# Microcontroller_board_Photodiode_plate.net
KiCad netlist of a schematic drawn in EasyEDA
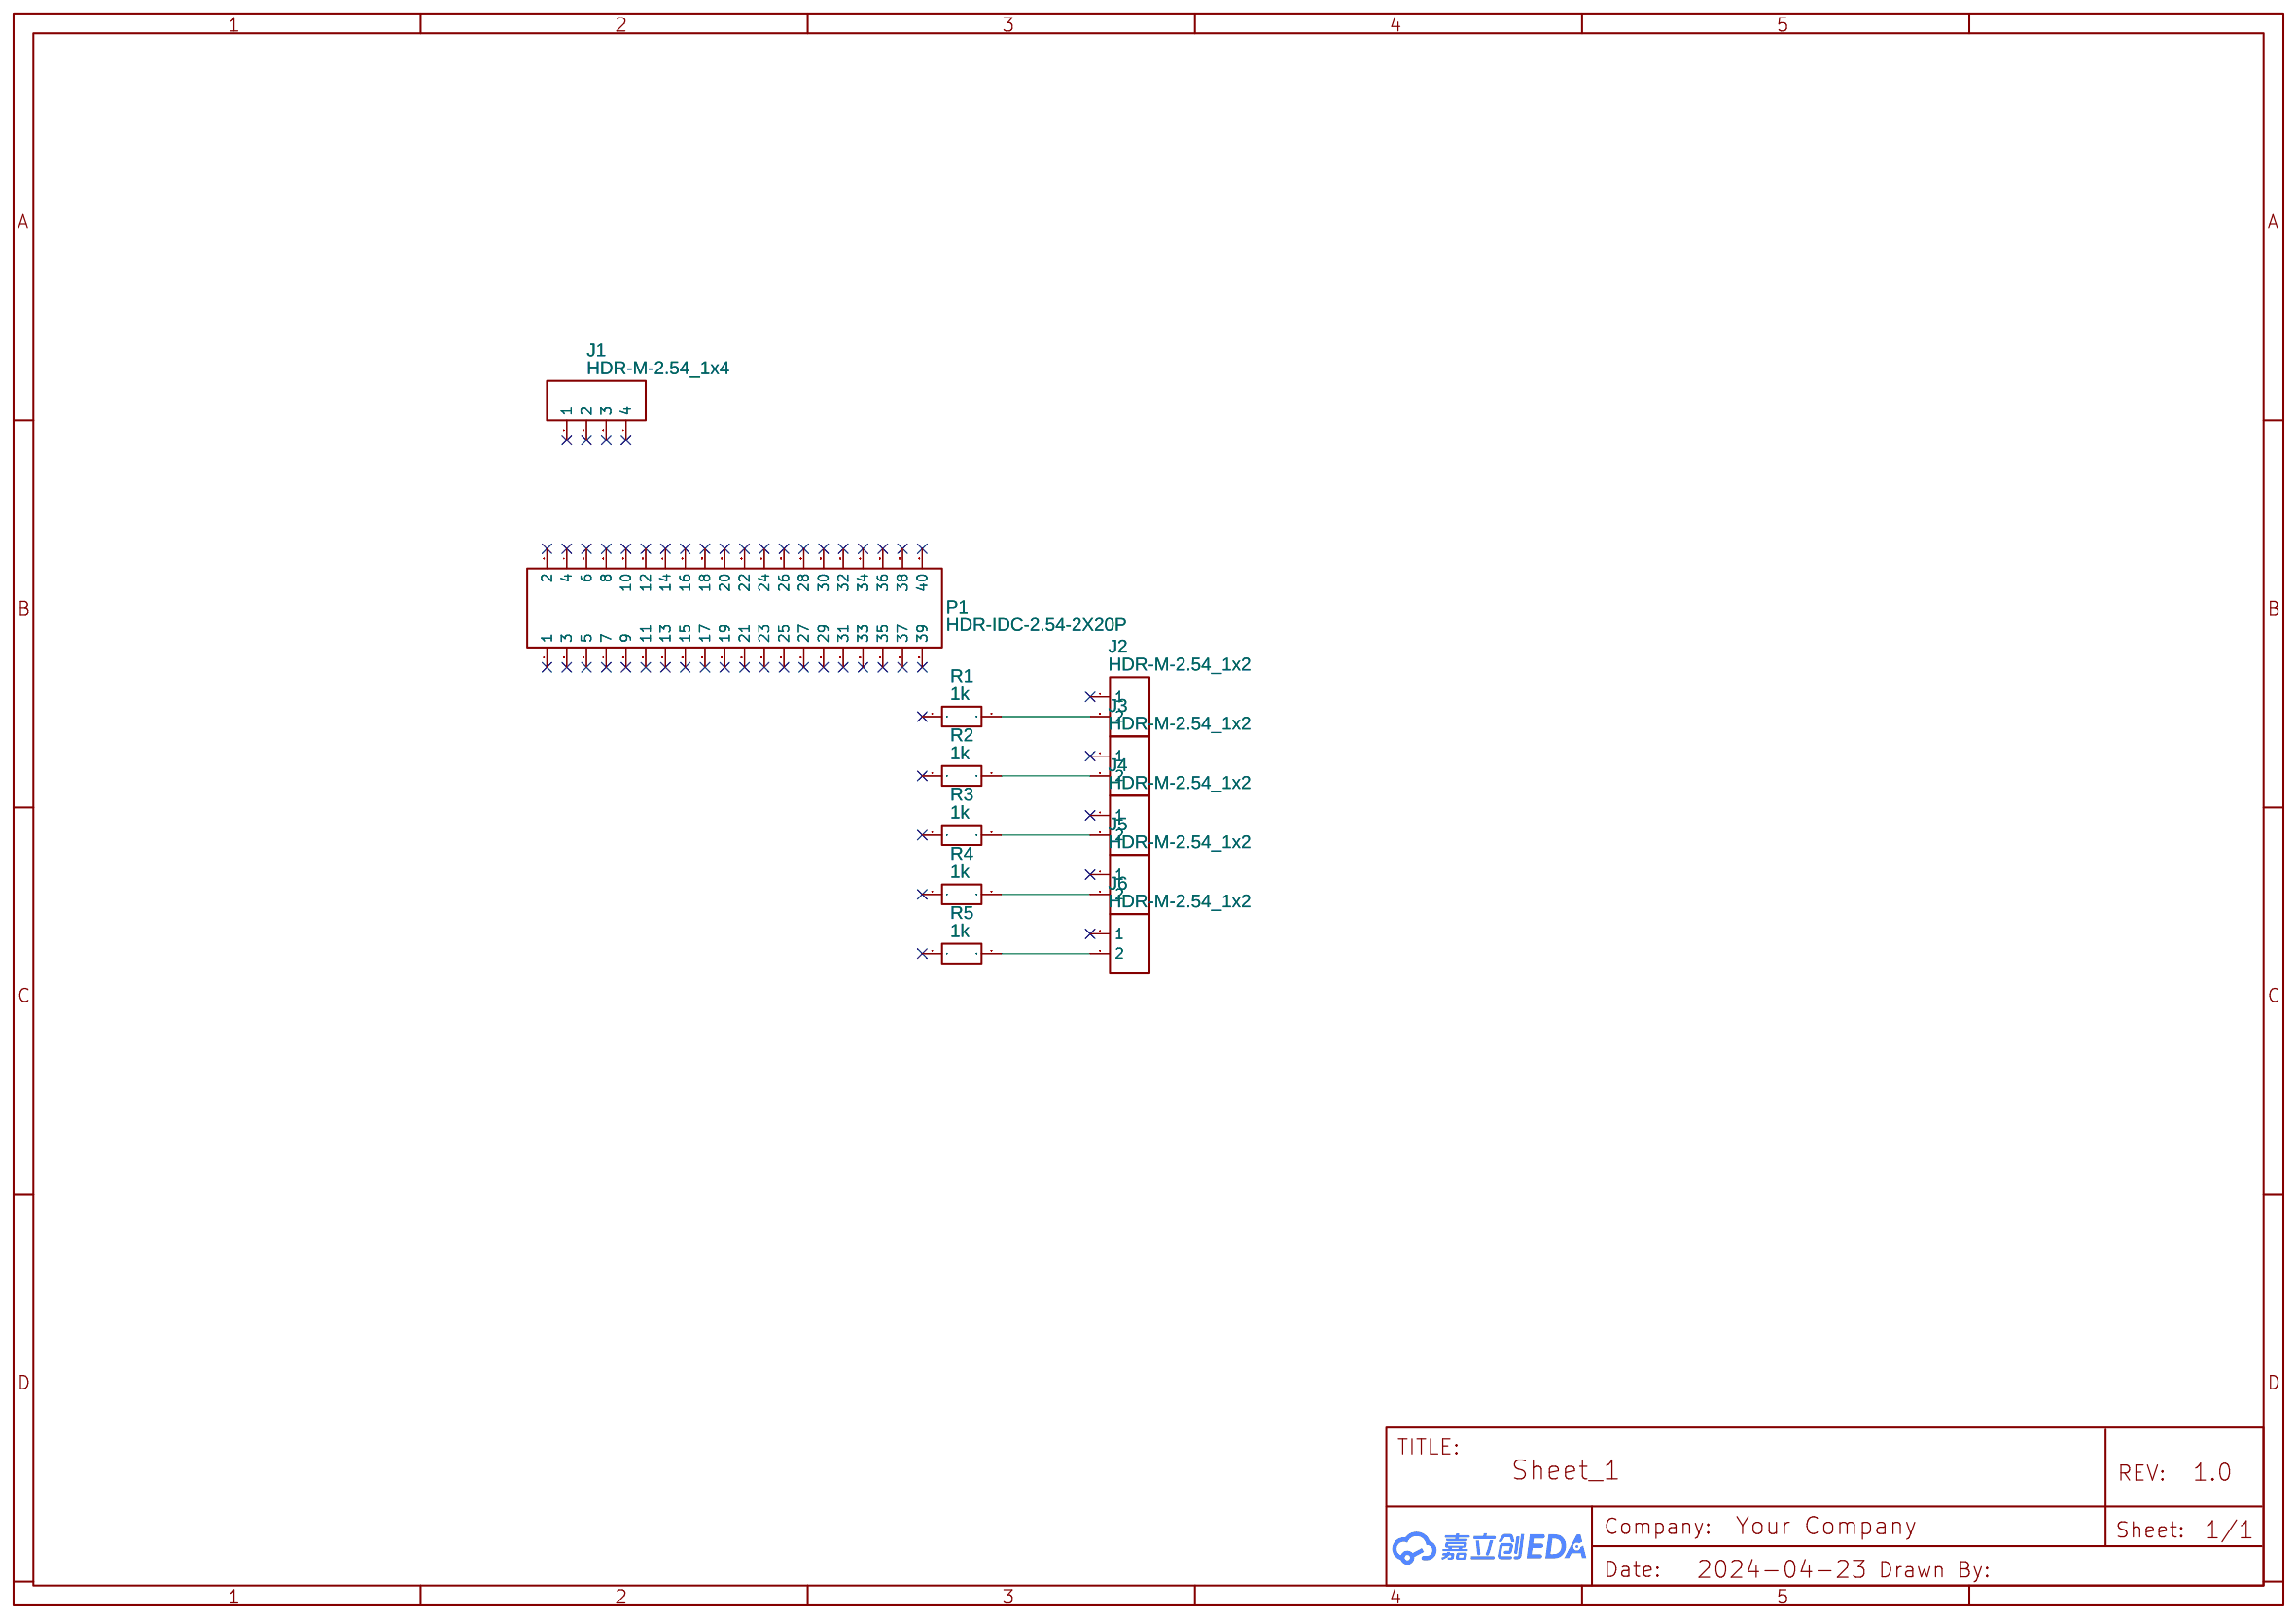
[diagram p0: schematic sheet]

(export (version "E")
  (design (tool "Eeschema 10.0.6"))
  (components
    (comp (ref "J1")
      (value "HDR-M-2.54_1x4")
      (fields (field (name "BOM_Supplier Part") "C124378"))
      (libsource (lib "") (part "HDR-M-2.54_1x4"))
    )
    (comp (ref "J2")
      (value "HDR-M-2.54_1x2")
      (fields (field (name "BOM_Supplier Part") "C124375"))
      (libsource (lib "") (part "HDR-M-2.54_1x2"))
    )
    (comp (ref "J3")
      (value "HDR-M-2.54_1x2")
      (fields (field (name "BOM_Supplier Part") "C124375"))
      (libsource (lib "") (part "HDR-M-2.54_1x2"))
    )
    (comp (ref "J4")
      (value "HDR-M-2.54_1x2")
      (fields (field (name "BOM_Supplier Part") "C124375"))
      (libsource (lib "") (part "HDR-M-2.54_1x2"))
    )
    (comp (ref "J5")
      (value "HDR-M-2.54_1x2")
      (fields (field (name "BOM_Supplier Part") "C124375"))
      (libsource (lib "") (part "HDR-M-2.54_1x2"))
    )
    (comp (ref "J6")
      (value "HDR-M-2.54_1x2")
      (fields (field (name "BOM_Supplier Part") "C124375"))
      (libsource (lib "") (part "HDR-M-2.54_1x2"))
    )
    (comp (ref "P1")
      (value "HDR-IDC-2.54-2X20P")
      (fields
        (field (name "BOM_Manufacturer Part") "IDC Box 2X20 2.54MM")
        (field (name "BOM_Supplier Part") "C9138")
      )
      (libsource (lib "") (part "HDR-IDC-2.54-2X20P"))
    )
    (comp (ref "R1") (value "1k") (libsource (lib "") (part "R_AXIAL-0.3_EU")))
    (comp (ref "R2") (value "1k") (libsource (lib "") (part "R_AXIAL-0.3_EU")))
    (comp (ref "R3") (value "1k") (libsource (lib "") (part "R_AXIAL-0.3_EU")))
    (comp (ref "R4") (value "1k") (libsource (lib "") (part "R_AXIAL-0.3_EU")))
    (comp (ref "R5") (value "1k") (libsource (lib "") (part "R_AXIAL-0.3_EU")))
  )
  (nets
    (net (code "1") (name "Net-(J2-Pad2)") (class "Default")
      (node (ref "J2") (pin "2") (pinfunction "2_2") (pintype "unspecified"))
      (node (ref "R1") (pin "2") (pinfunction "2_2") (pintype "unspecified"))
    )
    (net (code "2") (name "Net-(J3-Pad2)") (class "Default")
      (node (ref "J3") (pin "2") (pinfunction "2_2") (pintype "unspecified"))
      (node (ref "R2") (pin "2") (pinfunction "2_2") (pintype "unspecified"))
    )
    (net (code "3") (name "Net-(J4-Pad2)") (class "Default")
      (node (ref "J4") (pin "2") (pinfunction "2_2") (pintype "unspecified"))
      (node (ref "R3") (pin "2") (pinfunction "2_2") (pintype "unspecified"))
    )
    (net (code "4") (name "Net-(J5-Pad2)") (class "Default")
      (node (ref "J5") (pin "2") (pinfunction "2_2") (pintype "unspecified"))
      (node (ref "R4") (pin "2") (pinfunction "2_2") (pintype "unspecified"))
    )
    (net (code "5") (name "Net-(J6-Pad2)") (class "Default")
      (node (ref "J6") (pin "2") (pinfunction "2_2") (pintype "unspecified"))
      (node (ref "R5") (pin "2") (pinfunction "2_2") (pintype "unspecified"))
    )
    (net (code "6") (name "unconnected-(J1-Pad1)") (class "Default")
      (node (ref "J1") (pin "1") (pinfunction "1_1") (pintype "unspecified+no_connect"))
    )
    (net (code "7") (name "unconnected-(J1-Pad2)") (class "Default")
      (node (ref "J1") (pin "2") (pinfunction "2_2") (pintype "unspecified+no_connect"))
    )
    (net (code "8") (name "unconnected-(J1-Pad3)") (class "Default")
      (node (ref "J1") (pin "3") (pinfunction "3_3") (pintype "unspecified+no_connect"))
    )
    (net (code "9") (name "unconnected-(J1-Pad4)") (class "Default")
      (node (ref "J1") (pin "4") (pinfunction "4_4") (pintype "unspecified+no_connect"))
    )
    (net (code "10") (name "unconnected-(J2-Pad1)") (class "Default")
      (node (ref "J2") (pin "1") (pinfunction "1_1") (pintype "unspecified+no_connect"))
    )
    (net (code "11") (name "unconnected-(J3-Pad1)") (class "Default")
      (node (ref "J3") (pin "1") (pinfunction "1_1") (pintype "unspecified+no_connect"))
    )
    (net (code "12") (name "unconnected-(J4-Pad1)") (class "Default")
      (node (ref "J4") (pin "1") (pinfunction "1_1") (pintype "unspecified+no_connect"))
    )
    (net (code "13") (name "unconnected-(J5-Pad1)") (class "Default")
      (node (ref "J5") (pin "1") (pinfunction "1_1") (pintype "unspecified+no_connect"))
    )
    (net (code "14") (name "unconnected-(J6-Pad1)") (class "Default")
      (node (ref "J6") (pin "1") (pinfunction "1_1") (pintype "unspecified+no_connect"))
    )
    (net (code "15") (name "unconnected-(P1-Pad1)") (class "Default")
      (node (ref "P1") (pin "1") (pinfunction "1_1") (pintype "unspecified+no_connect"))
    )
    (net (code "16") (name "unconnected-(P1-Pad2)") (class "Default")
      (node (ref "P1") (pin "2") (pinfunction "2_2") (pintype "unspecified+no_connect"))
    )
    (net (code "17") (name "unconnected-(P1-Pad3)") (class "Default")
      (node (ref "P1") (pin "3") (pinfunction "3_3") (pintype "unspecified+no_connect"))
    )
    (net (code "18") (name "unconnected-(P1-Pad4)") (class "Default")
      (node (ref "P1") (pin "4") (pinfunction "4_4") (pintype "unspecified+no_connect"))
    )
    (net (code "19") (name "unconnected-(P1-Pad5)") (class "Default")
      (node (ref "P1") (pin "5") (pinfunction "5_5") (pintype "unspecified+no_connect"))
    )
    (net (code "20") (name "unconnected-(P1-Pad6)") (class "Default")
      (node (ref "P1") (pin "6") (pinfunction "6_6") (pintype "unspecified+no_connect"))
    )
    (net (code "21") (name "unconnected-(P1-Pad7)") (class "Default")
      (node (ref "P1") (pin "7") (pinfunction "7_7") (pintype "unspecified+no_connect"))
    )
    (net (code "22") (name "unconnected-(P1-Pad8)") (class "Default")
      (node (ref "P1") (pin "8") (pinfunction "8_8") (pintype "unspecified+no_connect"))
    )
    (net (code "23") (name "unconnected-(P1-Pad9)") (class "Default")
      (node (ref "P1") (pin "9") (pinfunction "9_9") (pintype "unspecified+no_connect"))
    )
    (net (code "24") (name "unconnected-(P1-Pad10)") (class "Default")
      (node (ref "P1") (pin "10") (pinfunction "10_10") (pintype "unspecified+no_connect"))
    )
    (net (code "25") (name "unconnected-(P1-Pad11)") (class "Default")
      (node (ref "P1") (pin "11") (pinfunction "11_11") (pintype "unspecified+no_connect"))
    )
    (net (code "26") (name "unconnected-(P1-Pad12)") (class "Default")
      (node (ref "P1") (pin "12") (pinfunction "12_12") (pintype "unspecified+no_connect"))
    )
    (net (code "27") (name "unconnected-(P1-Pad13)") (class "Default")
      (node (ref "P1") (pin "13") (pinfunction "13_13") (pintype "unspecified+no_connect"))
    )
    (net (code "28") (name "unconnected-(P1-Pad14)") (class "Default")
      (node (ref "P1") (pin "14") (pinfunction "14_14") (pintype "unspecified+no_connect"))
    )
    (net (code "29") (name "unconnected-(P1-Pad15)") (class "Default")
      (node (ref "P1") (pin "15") (pinfunction "15_15") (pintype "unspecified+no_connect"))
    )
    (net (code "30") (name "unconnected-(P1-Pad16)") (class "Default")
      (node (ref "P1") (pin "16") (pinfunction "16_16") (pintype "unspecified+no_connect"))
    )
    (net (code "31") (name "unconnected-(P1-Pad17)") (class "Default")
      (node (ref "P1") (pin "17") (pinfunction "17_17") (pintype "unspecified+no_connect"))
    )
    (net (code "32") (name "unconnected-(P1-Pad18)") (class "Default")
      (node (ref "P1") (pin "18") (pinfunction "18_18") (pintype "unspecified+no_connect"))
    )
    (net (code "33") (name "unconnected-(P1-Pad19)") (class "Default")
      (node (ref "P1") (pin "19") (pinfunction "19_19") (pintype "unspecified+no_connect"))
    )
    (net (code "34") (name "unconnected-(P1-Pad20)") (class "Default")
      (node (ref "P1") (pin "20") (pinfunction "20_20") (pintype "unspecified+no_connect"))
    )
    (net (code "35") (name "unconnected-(P1-Pad21)") (class "Default")
      (node (ref "P1") (pin "21") (pinfunction "21_21") (pintype "unspecified+no_connect"))
    )
    (net (code "36") (name "unconnected-(P1-Pad22)") (class "Default")
      (node (ref "P1") (pin "22") (pinfunction "22_22") (pintype "unspecified+no_connect"))
    )
    (net (code "37") (name "unconnected-(P1-Pad23)") (class "Default")
      (node (ref "P1") (pin "23") (pinfunction "23_23") (pintype "unspecified+no_connect"))
    )
    (net (code "38") (name "unconnected-(P1-Pad24)") (class "Default")
      (node (ref "P1") (pin "24") (pinfunction "24_24") (pintype "unspecified+no_connect"))
    )
    (net (code "39") (name "unconnected-(P1-Pad25)") (class "Default")
      (node (ref "P1") (pin "25") (pinfunction "25_25") (pintype "unspecified+no_connect"))
    )
    (net (code "40") (name "unconnected-(P1-Pad26)") (class "Default")
      (node (ref "P1") (pin "26") (pinfunction "26_26") (pintype "unspecified+no_connect"))
    )
    (net (code "41") (name "unconnected-(P1-Pad27)") (class "Default")
      (node (ref "P1") (pin "27") (pinfunction "27_27") (pintype "unspecified+no_connect"))
    )
    (net (code "42") (name "unconnected-(P1-Pad28)") (class "Default")
      (node (ref "P1") (pin "28") (pinfunction "28_28") (pintype "unspecified+no_connect"))
    )
    (net (code "43") (name "unconnected-(P1-Pad29)") (class "Default")
      (node (ref "P1") (pin "29") (pinfunction "29_29") (pintype "unspecified+no_connect"))
    )
    (net (code "44") (name "unconnected-(P1-Pad30)") (class "Default")
      (node (ref "P1") (pin "30") (pinfunction "30_30") (pintype "unspecified+no_connect"))
    )
    (net (code "45") (name "unconnected-(P1-Pad31)") (class "Default")
      (node (ref "P1") (pin "31") (pinfunction "31_31") (pintype "unspecified+no_connect"))
    )
    (net (code "46") (name "unconnected-(P1-Pad32)") (class "Default")
      (node (ref "P1") (pin "32") (pinfunction "32_32") (pintype "unspecified+no_connect"))
    )
    (net (code "47") (name "unconnected-(P1-Pad33)") (class "Default")
      (node (ref "P1") (pin "33") (pinfunction "33_33") (pintype "unspecified+no_connect"))
    )
    (net (code "48") (name "unconnected-(P1-Pad34)") (class "Default")
      (node (ref "P1") (pin "34") (pinfunction "34_34") (pintype "unspecified+no_connect"))
    )
    (net (code "49") (name "unconnected-(P1-Pad35)") (class "Default")
      (node (ref "P1") (pin "35") (pinfunction "35_35") (pintype "unspecified+no_connect"))
    )
    (net (code "50") (name "unconnected-(P1-Pad36)") (class "Default")
      (node (ref "P1") (pin "36") (pinfunction "36_36") (pintype "unspecified+no_connect"))
    )
    (net (code "51") (name "unconnected-(P1-Pad37)") (class "Default")
      (node (ref "P1") (pin "37") (pinfunction "37_37") (pintype "unspecified+no_connect"))
    )
    (net (code "52") (name "unconnected-(P1-Pad38)") (class "Default")
      (node (ref "P1") (pin "38") (pinfunction "38_38") (pintype "unspecified+no_connect"))
    )
    (net (code "53") (name "unconnected-(P1-Pad39)") (class "Default")
      (node (ref "P1") (pin "39") (pinfunction "39_39") (pintype "unspecified+no_connect"))
    )
    (net (code "54") (name "unconnected-(P1-Pad40)") (class "Default")
      (node (ref "P1") (pin "40") (pinfunction "40_40") (pintype "unspecified+no_connect"))
    )
    (net (code "55") (name "unconnected-(R1-Pad1)") (class "Default")
      (node (ref "R1") (pin "1") (pinfunction "1_1") (pintype "unspecified+no_connect"))
    )
    (net (code "56") (name "unconnected-(R2-Pad1)") (class "Default")
      (node (ref "R2") (pin "1") (pinfunction "1_1") (pintype "unspecified+no_connect"))
    )
    (net (code "57") (name "unconnected-(R3-Pad1)") (class "Default")
      (node (ref "R3") (pin "1") (pinfunction "1_1") (pintype "unspecified+no_connect"))
    )
    (net (code "58") (name "unconnected-(R4-Pad1)") (class "Default")
      (node (ref "R4") (pin "1") (pinfunction "1_1") (pintype "unspecified+no_connect"))
    )
    (net (code "59") (name "unconnected-(R5-Pad1)") (class "Default")
      (node (ref "R5") (pin "1") (pinfunction "1_1") (pintype "unspecified+no_connect"))
    )
  )
)
